# GSM.net
KiCad netlist of a schematic drawn in Altium Designer
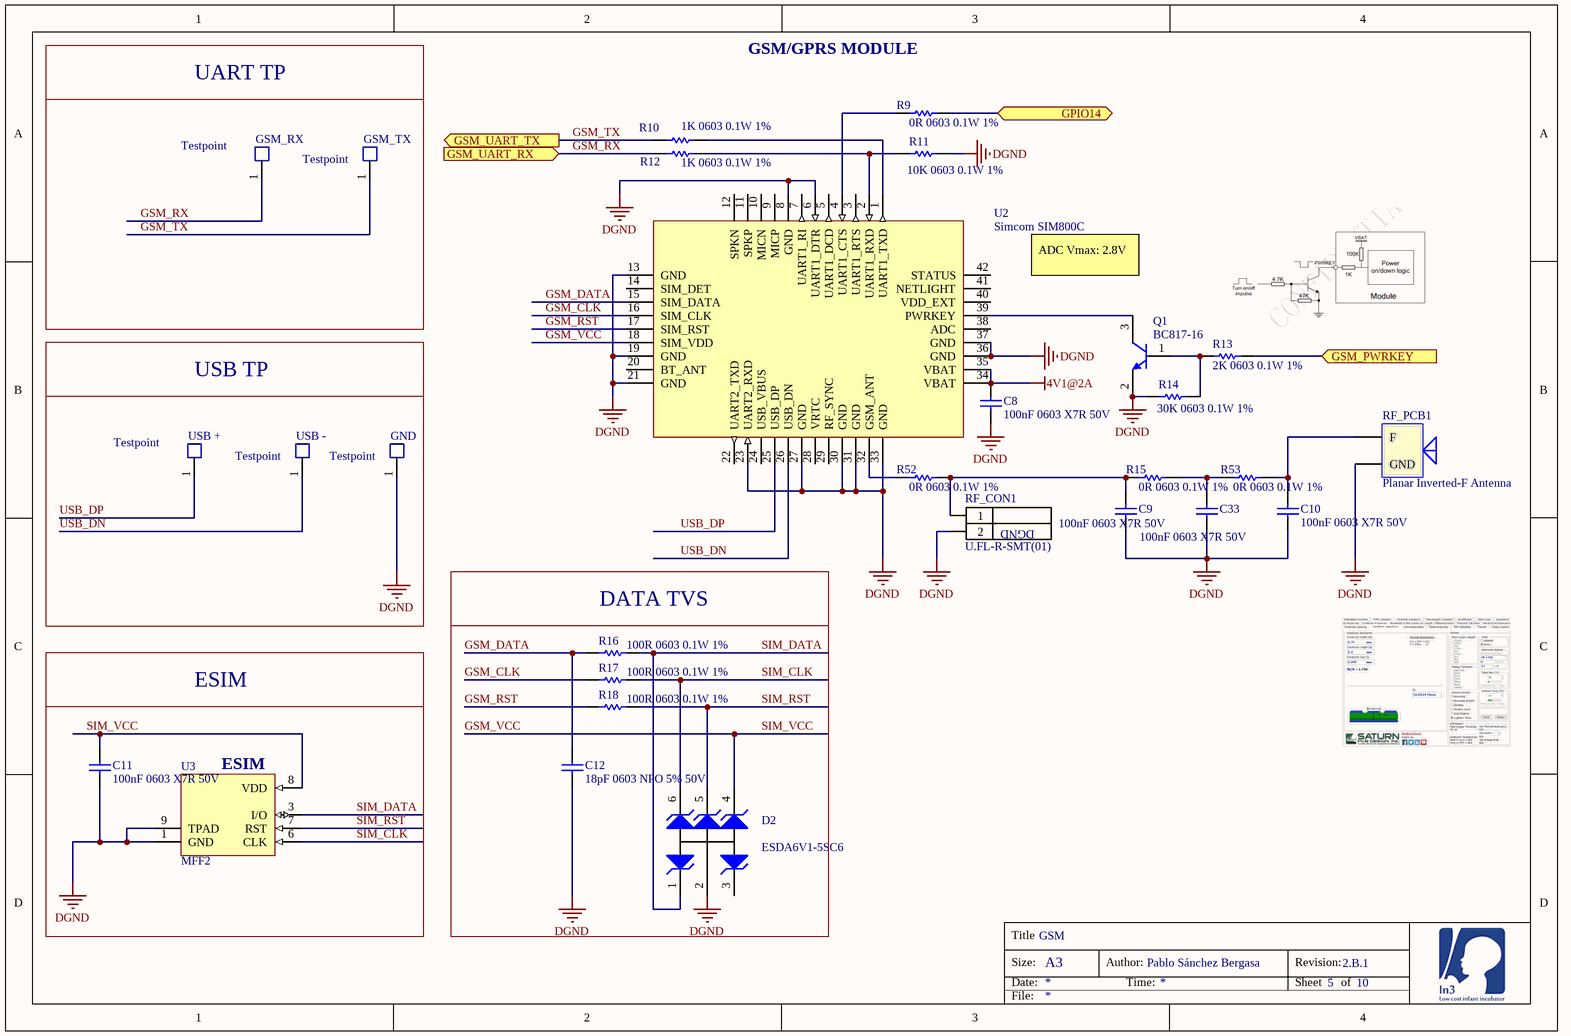
[diagram p0: GSM.SchDoc]

(export (version "E")
  (design (tool "Eeschema 10.0.6"))
  (components
    (comp (ref "C8")
      (value "100nF 0603 X7R 50V")
      (footprint "CAPC1608X60X35NL10T15")
      (description "100nF 0603 X7R 25V")
      (libsource (lib "CommunityVault") (part "CMP-c41a0d2b65641bdd-3"))
    )
    (comp (ref "C9")
      (value "100nF 0603 X7R 50V")
      (footprint "CAPC1608X60X35NL10T15")
      (description "100nF 0603 X7R 25V")
      (libsource (lib "CommunityVault") (part "CMP-c41a0d2b65641bdd-3"))
    )
    (comp (ref "C10")
      (value "100nF 0603 X7R 50V")
      (footprint "CAPC1608X60X35NL10T15")
      (description "100nF 0603 X7R 25V")
      (libsource (lib "CommunityVault") (part "CMP-c41a0d2b65641bdd-3"))
    )
    (comp (ref "C11")
      (value "100nF 0603 X7R 50V")
      (footprint "CAPC1608X60X35NL10T15")
      (description "100nF 0603 X7R 25V")
      (libsource (lib "CommunityVault") (part "CMP-c41a0d2b65641bdd-3"))
    )
    (comp (ref "C12")
      (value "18pF 0603 NPO 5% 50V")
      (footprint "CAPC1608X60X35NL10T15")
      (fields (field (name "MANUFACTURER PART NUMBER") "C0603C180K5RACTU"))
      (libsource (lib "CommunityVault") (part "CMP-35cbf9f8b0acea0c-1"))
    )
    (comp (ref "C33")
      (value "100nF 0603 X7R 50V")
      (footprint "CAPC1608X60X35NL10T15")
      (description "100nF 0603 X7R 25V")
      (libsource (lib "CommunityVault") (part "CMP-c41a0d2b65641bdd-3"))
    )
    (comp (ref "D2")
      (value "ESDA6V1-5SC6")
      (footprint "MF06A_N")
      (description "ESDA Series 5 Channel 6.1 V 50 pF SMT Uni Directional Transil Array - SOT-23-6L")
      (libsource (lib "CommunityVault") (part "CMP-924f5b40f9684d88-1"))
    )
    (comp (ref "GND")
      (value "Testpoint")
      (footprint "PCB-nm3bqur1hdh465dxvdoy-1")
      (description "WR-PHD_1.27MM_JUMPER_BLACK W/ Pu")
      (libsource (lib "CommunityVault") (part "CMP-0fe9c5016150d02e-1"))
    )
    (comp (ref "GSM_RX")
      (value "Testpoint")
      (footprint "PCB-nm3bqur1hdh465dxvdoy-1")
      (description "WR-PHD_1.27MM_JUMPER_BLACK W/ Pu")
      (libsource (lib "CommunityVault") (part "CMP-0fe9c5016150d02e-1"))
    )
    (comp (ref "GSM_TX")
      (value "Testpoint")
      (footprint "PCB-nm3bqur1hdh465dxvdoy-1")
      (description "WR-PHD_1.27MM_JUMPER_BLACK W/ Pu")
      (libsource (lib "CommunityVault") (part "CMP-0fe9c5016150d02e-1"))
    )
    (comp (ref "Q1")
      (value "BC817-16")
      (footprint "PCB-856332-1")
      (description "TRANS NPN 45V 500mA SMD SOT23-3")
      (libsource (lib "CommunityVault") (part "CMP-856332-3"))
    )
    (comp (ref "R9")
      (value "0R 0603 0.1W 1%")
      (footprint "RESC1609X55X30ML10T20")
      (libsource (lib "CommunityVault") (part "CMP-536b9a7387ce8cac-10"))
    )
    (comp (ref "R10")
      (value "1K 0603 0.1W 1%")
      (footprint "RESC1609X55X30ML10T20")
      (fields (field (name "MANUFACTURER PART NUMBER") "CR0603-FX-1001ELF"))
      (libsource (lib "CommunityVault") (part "CMP-a61f6f36030f79d8-4"))
    )
    (comp (ref "R11")
      (value "10K 0603 0.1W 1%")
      (footprint "RESC1609X55X30ML10T20")
      (fields (field (name "TOLERANCE") "1%"))
      (libsource (lib "CommunityVault") (part "CMP-4716590-9"))
    )
    (comp (ref "R12")
      (value "1K 0603 0.1W 1%")
      (footprint "RESC1609X55X30ML10T20")
      (fields (field (name "MANUFACTURER PART NUMBER") "CR0603-FX-1001ELF"))
      (libsource (lib "CommunityVault") (part "CMP-a61f6f36030f79d8-4"))
    )
    (comp (ref "R13")
      (value "2K 0603 0.1W 1%")
      (footprint "RESC1609X55X30ML10T20")
      (fields (field (name "TOLERANCE") "1%"))
      (libsource (lib "CommunityVault") (part "CMP-3655986-6"))
    )
    (comp (ref "R14")
      (value "30K 0603 0.1W 1%")
      (footprint "RESC1609X55X30ML10T20")
      (fields (field (name "TOLERANCE") "1%"))
      (libsource (lib "CommunityVault") (part "CMP-3655986-6"))
    )
    (comp (ref "R15")
      (value "0R 0603 0.1W 1%")
      (footprint "RESC1609X55X30ML10T20")
      (libsource (lib "CommunityVault") (part "CMP-536b9a7387ce8cac-10"))
    )
    (comp (ref "R16")
      (value "100R 0603 0.1W 1%")
      (footprint "RESC1609X55X30ML10T20")
      (fields (field (name "MANUFACTURER PART NUMBER") "ERJ3GEYJ101V"))
      (libsource (lib "CommunityVault") (part "CMP-a61f6f36030f79d8-4"))
    )
    (comp (ref "R17")
      (value "100R 0603 0.1W 1%")
      (footprint "RESC1609X55X30ML10T20")
      (fields (field (name "MANUFACTURER PART NUMBER") "ERJ3GEYJ101V"))
      (libsource (lib "CommunityVault") (part "CMP-a61f6f36030f79d8-4"))
    )
    (comp (ref "R18")
      (value "100R 0603 0.1W 1%")
      (footprint "RESC1609X55X30ML10T20")
      (fields (field (name "MANUFACTURER PART NUMBER") "ERJ3GEYJ101V"))
      (libsource (lib "CommunityVault") (part "CMP-a61f6f36030f79d8-4"))
    )
    (comp (ref "R52")
      (value "0R 0603 0.1W 1%")
      (footprint "RESC1609X55X30ML10T20")
      (libsource (lib "CommunityVault") (part "CMP-536b9a7387ce8cac-10"))
    )
    (comp (ref "R53")
      (value "0R 0603 0.1W 1%")
      (footprint "RESC1609X55X30ML10T20")
      (libsource (lib "CommunityVault") (part "CMP-536b9a7387ce8cac-10"))
    )
    (comp (ref "RF_CON1")
      (value "U.FL-R-SMT(01)")
      (footprint "PCB-ci0d6ius1xp1vci7q9ug-1")
      (description "Connector RF Coaxial Data Midget Coaxial")
      (libsource (lib "CommunityVault") (part "CMP-b06f7b3edcee6fa8-4"))
    )
    (comp (ref "RF_PCB1")
      (value "Planar Inverted-F Antenna")
      (footprint "PCB-k9titb4465gfk1ijwrnj-1")
      (description "GSM900 and GSM1800  Frequency Bands PCB antenna")
      (libsource (lib "FavoritesLibrary") (part "SYM-ec54202eacef3393-1"))
    )
    (comp (ref "U2")
      (value "Simcom SIM800C")
      (footprint "SIM800C")
      (description "Module: GSM/Bluetooth; GPRS; 2G; 1800MHz, 900MHz; 85.6kbps; SMD")
      (fields (field (name "MANUFACTURER PART NUMBER") "SIM800C"))
      (libsource (lib "FavoritesLibrary") (part "SYM-72dbb8ea0133ad1c-1"))
    )
    (comp (ref "U3")
      (value "MFF2")
      (footprint "SON127P600X95_HS-9N")
      (description "Embedded SIM card in MFF2")
      (libsource (lib "CommunityVault") (part "CMP-ce8f06c57f401148-2"))
    )
    (comp (ref "USB +")
      (value "Testpoint")
      (footprint "PCB-nm3bqur1hdh465dxvdoy-1")
      (description "WR-PHD_1.27MM_JUMPER_BLACK W/ Pu")
      (libsource (lib "CommunityVault") (part "CMP-0fe9c5016150d02e-1"))
    )
    (comp (ref "USB -")
      (value "Testpoint")
      (footprint "PCB-nm3bqur1hdh465dxvdoy-1")
      (description "WR-PHD_1.27MM_JUMPER_BLACK W/ Pu")
      (libsource (lib "CommunityVault") (part "CMP-0fe9c5016150d02e-1"))
    )
  )
  (nets
    (net (code "1") (name "/GPIO14") (class "Default")
      (node (ref "R9") (pin "2") (pinfunction "2_2") (pintype "passive"))
    )
    (net (code "2") (name "/GSM_CLK") (class "Default")
      (node (ref "R17") (pin "2") (pinfunction "2_2") (pintype "passive"))
      (node (ref "U2") (pin "16") (pinfunction "SIM_CLK_16") (pintype "passive"))
    )
    (net (code "3") (name "/GSM_DATA") (class "Default")
      (node (ref "C12") (pin "2") (pinfunction "2_2") (pintype "passive"))
      (node (ref "R16") (pin "2") (pinfunction "2_2") (pintype "passive"))
      (node (ref "U2") (pin "15") (pinfunction "SIM_DATA_15") (pintype "passive"))
    )
    (net (code "4") (name "/GSM_PWRKEY") (class "Default")
      (node (ref "R13") (pin "1") (pinfunction "1_1") (pintype "passive"))
    )
    (net (code "5") (name "/GSM_RST") (class "Default")
      (node (ref "R18") (pin "2") (pinfunction "2_2") (pintype "passive"))
      (node (ref "U2") (pin "17") (pinfunction "SIM_RST_17") (pintype "passive"))
    )
    (net (code "6") (name "/GSM_RX") (class "Default")
      (node (ref "GSM_RX") (pin "1") (pintype "passive"))
      (node (ref "R12") (pin "1") (pinfunction "1_1") (pintype "passive"))
    )
    (net (code "7") (name "/GSM_TX") (class "Default")
      (node (ref "GSM_TX") (pin "1") (pintype "passive"))
      (node (ref "R10") (pin "1") (pinfunction "1_1") (pintype "passive"))
    )
    (net (code "8") (name "/GSM_VCC") (class "Default")
      (node (ref "C11") (pin "2") (pinfunction "2_2") (pintype "passive"))
      (node (ref "D2") (pin "4") (pinfunction "A_4") (pintype "passive"))
      (node (ref "U2") (pin "18") (pinfunction "SIM_VDD_18") (pintype "passive"))
      (node (ref "U3") (pin "8") (pinfunction "VDD_8") (pintype "input"))
    )
    (net (code "9") (name "/SIM_CLK") (class "Default")
      (node (ref "D2") (pin "6") (pinfunction "A_6") (pintype "passive"))
      (node (ref "R17") (pin "1") (pinfunction "1_1") (pintype "passive"))
      (node (ref "U3") (pin "6") (pinfunction "CLK_6") (pintype "input"))
    )
    (net (code "10") (name "/SIM_DATA") (class "Default")
      (node (ref "D2") (pin "1") (pinfunction "K_1") (pintype "passive"))
      (node (ref "R16") (pin "1") (pinfunction "1_1") (pintype "passive"))
      (node (ref "U3") (pin "3") (pinfunction "I/O_3") (pintype "bidirectional"))
    )
    (net (code "11") (name "/SIM_RST") (class "Default")
      (node (ref "D2") (pin "5") (pinfunction "A_5") (pintype "passive"))
      (node (ref "R18") (pin "1") (pinfunction "1_1") (pintype "passive"))
      (node (ref "U3") (pin "7") (pinfunction "RST_7") (pintype "input"))
    )
    (net (code "12") (name "/USB_DN") (class "Default")
      (node (ref "U2") (pin "26") (pinfunction "USB_DN_26") (pintype "passive"))
      (node (ref "USB -") (pin "1") (pintype "passive"))
    )
    (net (code "13") (name "/USB_DP") (class "Default")
      (node (ref "U2") (pin "25") (pinfunction "USB_DP_25") (pintype "passive"))
      (node (ref "USB +") (pin "1") (pintype "passive"))
    )
    (net (code "14") (name "4V1@2A") (class "Default")
      (node (ref "C8") (pin "2") (pinfunction "2_2") (pintype "passive"))
      (node (ref "U2") (pin "34") (pinfunction "VBAT_34") (pintype "passive"))
      (node (ref "U2") (pin "35") (pinfunction "VBAT_35") (pintype "passive"))
    )
    (net (code "15") (name "DGND") (class "Default")
      (node (ref "C10") (pin "1") (pinfunction "1_1") (pintype "passive"))
      (node (ref "C11") (pin "1") (pinfunction "1_1") (pintype "passive"))
      (node (ref "C12") (pin "1") (pinfunction "1_1") (pintype "passive"))
      (node (ref "C33") (pin "1") (pinfunction "1_1") (pintype "passive"))
      (node (ref "C8") (pin "1") (pinfunction "1_1") (pintype "passive"))
      (node (ref "C9") (pin "1") (pinfunction "1_1") (pintype "passive"))
      (node (ref "D2") (pin "2") (pinfunction "K_2") (pintype "passive"))
      (node (ref "GND") (pin "1") (pintype "passive"))
      (node (ref "Q1") (pin "2") (pinfunction "E_2") (pintype "passive"))
      (node (ref "R11") (pin "2") (pinfunction "2_2") (pintype "passive"))
      (node (ref "R14") (pin "2") (pinfunction "2_2") (pintype "passive"))
      (node (ref "RF_CON1") (pin "2") (pinfunction "2_2") (pintype "passive"))
      (node (ref "RF_PCB1") (pin "2") (pinfunction "GND_2") (pintype "passive"))
      (node (ref "U2") (pin "13") (pinfunction "GND_13") (pintype "passive"))
      (node (ref "U2") (pin "19") (pinfunction "GND_19") (pintype "passive"))
      (node (ref "U2") (pin "21") (pinfunction "GND_21") (pintype "passive"))
      (node (ref "U2") (pin "23") (pinfunction "UART2_RXD_23") (pintype "input"))
      (node (ref "U2") (pin "27") (pinfunction "GND_27") (pintype "power_in"))
      (node (ref "U2") (pin "30") (pinfunction "GND_30") (pintype "power_in"))
      (node (ref "U2") (pin "31") (pinfunction "GND_31") (pintype "power_in"))
      (node (ref "U2") (pin "33") (pinfunction "GND_33") (pintype "power_in"))
      (node (ref "U2") (pin "36") (pinfunction "GND_36") (pintype "power_in"))
      (node (ref "U2") (pin "37") (pinfunction "GND_37") (pintype "power_in"))
      (node (ref "U2") (pin "6") (pinfunction "UART1_DTR_6") (pintype "input"))
      (node (ref "U2") (pin "8") (pinfunction "GND_8") (pintype "power_in"))
      (node (ref "U3") (pin "1") (pinfunction "GND_1") (pintype "power_in"))
      (node (ref "U3") (pin "9") (pinfunction "TPAD_9") (pintype "power_in"))
    )
    (net (code "16") (name "Net-(C9-Pad2)") (class "Default")
      (node (ref "C9") (pin "2") (pinfunction "2_2") (pintype "passive"))
      (node (ref "R15") (pin "1") (pinfunction "1_1") (pintype "passive"))
      (node (ref "R52") (pin "2") (pinfunction "2_2") (pintype "passive"))
      (node (ref "RF_CON1") (pin "1") (pinfunction "1_1") (pintype "passive"))
    )
    (net (code "17") (name "Net-(C33-Pad2)") (class "Default")
      (node (ref "C33") (pin "2") (pinfunction "2_2") (pintype "passive"))
      (node (ref "R15") (pin "2") (pinfunction "2_2") (pintype "passive"))
      (node (ref "R53") (pin "1") (pinfunction "1_1") (pintype "passive"))
    )
    (net (code "18") (name "Net-(Q1-B)") (class "Default")
      (node (ref "Q1") (pin "1") (pinfunction "B_1") (pintype "passive"))
      (node (ref "R13") (pin "2") (pinfunction "2_2") (pintype "passive"))
      (node (ref "R14") (pin "1") (pinfunction "1_1") (pintype "passive"))
    )
    (net (code "19") (name "Net-(Q1-C)") (class "Default")
      (node (ref "Q1") (pin "3") (pinfunction "C_3") (pintype "passive"))
      (node (ref "U2") (pin "39") (pinfunction "PWRKEY_39") (pintype "passive"))
    )
    (net (code "20") (name "Net-(RF_PCB1-F)") (class "Default")
      (node (ref "C10") (pin "2") (pinfunction "2_2") (pintype "passive"))
      (node (ref "R53") (pin "2") (pinfunction "2_2") (pintype "passive"))
      (node (ref "RF_PCB1") (pin "1") (pinfunction "F_1") (pintype "passive"))
    )
    (net (code "21") (name "Net-(U2-GSM_ANT)") (class "Default")
      (node (ref "R52") (pin "1") (pinfunction "1_1") (pintype "passive"))
      (node (ref "U2") (pin "32") (pinfunction "GSM_ANT_32") (pintype "passive"))
    )
    (net (code "22") (name "Net-(U2-UART1_CTS)") (class "Default")
      (node (ref "R9") (pin "1") (pinfunction "1_1") (pintype "passive"))
      (node (ref "U2") (pin "4") (pinfunction "UART1_CTS_4") (pintype "input"))
    )
    (net (code "23") (name "Net-(U2-UART1_RXD)") (class "Default")
      (node (ref "R11") (pin "1") (pinfunction "1_1") (pintype "passive"))
      (node (ref "R12") (pin "2") (pinfunction "2_2") (pintype "passive"))
      (node (ref "U2") (pin "2") (pinfunction "UART1_RXD_2") (pintype "input"))
    )
    (net (code "24") (name "Net-(U2-UART1_TXD)") (class "Default")
      (node (ref "R10") (pin "2") (pinfunction "2_2") (pintype "passive"))
      (node (ref "U2") (pin "1") (pinfunction "UART1_TXD_1") (pintype "output"))
    )
    (net (code "25") (name "unconnected-(D2-K-Pad3)") (class "Default")
      (node (ref "D2") (pin "3") (pinfunction "K_3") (pintype "passive"))
    )
    (net (code "26") (name "unconnected-(U2-ADC-Pad38)") (class "Default")
      (node (ref "U2") (pin "38") (pinfunction "ADC_38") (pintype "passive"))
    )
    (net (code "27") (name "unconnected-(U2-BT_ANT-Pad20)") (class "Default")
      (node (ref "U2") (pin "20") (pinfunction "BT_ANT_20") (pintype "passive"))
    )
    (net (code "28") (name "unconnected-(U2-MICN-Pad10)") (class "Default")
      (node (ref "U2") (pin "10") (pinfunction "MICN_10") (pintype "passive"))
    )
    (net (code "29") (name "unconnected-(U2-MICP-Pad9)") (class "Default")
      (node (ref "U2") (pin "9") (pinfunction "MICP_9") (pintype "passive"))
    )
    (net (code "30") (name "unconnected-(U2-NETLIGHT-Pad41)") (class "Default")
      (node (ref "U2") (pin "41") (pinfunction "NETLIGHT_41") (pintype "passive"))
    )
    (net (code "31") (name "unconnected-(U2-RF_SYNC-Pad29)") (class "Default")
      (node (ref "U2") (pin "29") (pinfunction "RF_SYNC_29") (pintype "passive"))
    )
    (net (code "32") (name "unconnected-(U2-SIM_DET-Pad14)") (class "Default")
      (node (ref "U2") (pin "14") (pinfunction "SIM_DET_14") (pintype "passive"))
    )
    (net (code "33") (name "unconnected-(U2-SPKN-Pad12)") (class "Default")
      (node (ref "U2") (pin "12") (pinfunction "SPKN_12") (pintype "passive"))
    )
    (net (code "34") (name "unconnected-(U2-SPKP-Pad11)") (class "Default")
      (node (ref "U2") (pin "11") (pinfunction "SPKP_11") (pintype "passive"))
    )
    (net (code "35") (name "unconnected-(U2-STATUS-Pad42)") (class "Default")
      (node (ref "U2") (pin "42") (pinfunction "STATUS_42") (pintype "passive"))
    )
    (net (code "36") (name "unconnected-(U2-UART1_DCD-Pad5)") (class "Default")
      (node (ref "U2") (pin "5") (pinfunction "UART1_DCD_5") (pintype "output"))
    )
    (net (code "37") (name "unconnected-(U2-UART1_RI-Pad7)") (class "Default")
      (node (ref "U2") (pin "7") (pinfunction "UART1_RI_7") (pintype "output"))
    )
    (net (code "38") (name "unconnected-(U2-UART1_RTS-Pad3)") (class "Default")
      (node (ref "U2") (pin "3") (pinfunction "UART1_RTS_3") (pintype "output"))
    )
    (net (code "39") (name "unconnected-(U2-UART2_TXD-Pad22)") (class "Default")
      (node (ref "U2") (pin "22") (pinfunction "UART2_TXD_22") (pintype "output"))
    )
    (net (code "40") (name "unconnected-(U2-USB_VBUS-Pad24)") (class "Default")
      (node (ref "U2") (pin "24") (pinfunction "USB_VBUS_24") (pintype "passive"))
    )
    (net (code "41") (name "unconnected-(U2-VDD_EXT-Pad40)") (class "Default")
      (node (ref "U2") (pin "40") (pinfunction "VDD_EXT_40") (pintype "passive"))
    )
    (net (code "42") (name "unconnected-(U2-VRTC-Pad28)") (class "Default")
      (node (ref "U2") (pin "28") (pinfunction "VRTC_28") (pintype "passive"))
    )
  )
)
